# PSU_2.net
KiCad netlist of a schematic drawn in Altium Designer
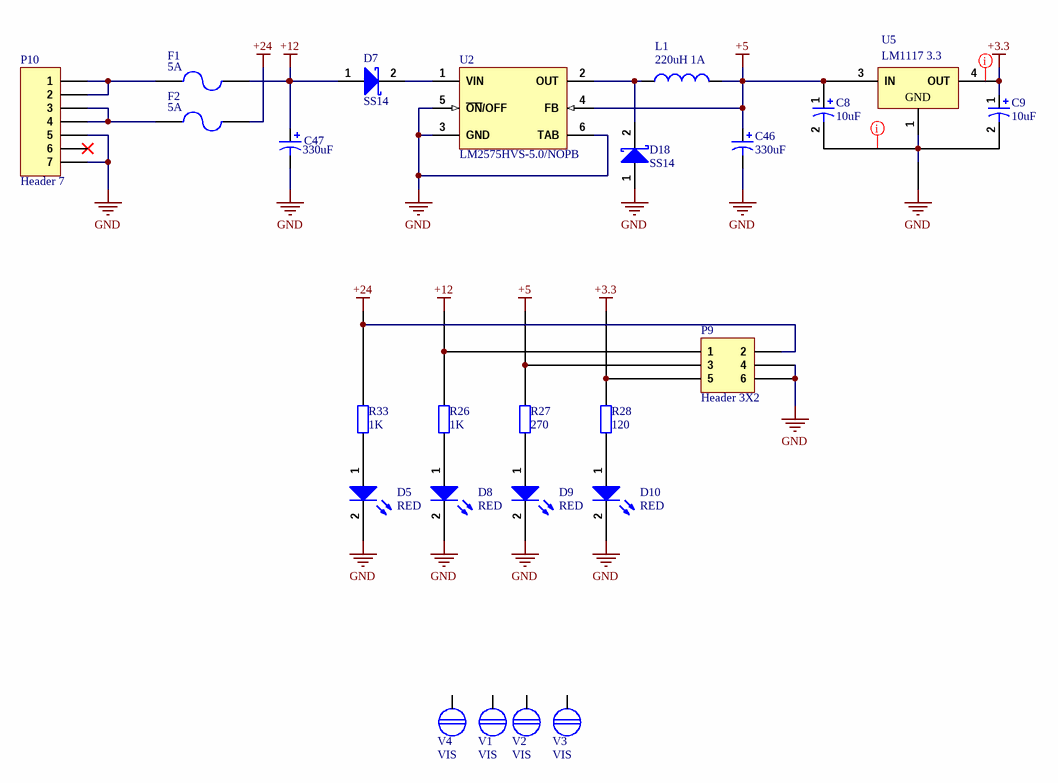
[diagram p0: PSU_2.SchDoc]

(export (version "E")
  (design (tool "Eeschema 10.0.6"))
  (components
    (comp (ref "C8")
      (value "10uF")
      (footprint "SYLANN:KEMET_4")
      (description "Polarized Capacitor")
      (fields
        (field (name "MANUFACTURER") "KEMET")
        (field (name "MANUFACTURER PART NUMBER") "EXV106M025A9BAA")
      )
      (libsource (lib "Miscellaneous Devices") (part "Cap Pol1"))
    )
    (comp (ref "C9")
      (value "10uF")
      (footprint "SYLANN:KEMET_4")
      (description "Polarized Capacitor")
      (fields
        (field (name "MANUFACTURER") "KEMET")
        (field (name "MANUFACTURER PART NUMBER") "EXV106M025A9BAA")
      )
      (libsource (lib "Miscellaneous Devices") (part "Cap Pol1"))
    )
    (comp (ref "C46")
      (value "330uF")
      (footprint "Kemet_10")
      (description "Polarized Capacitor (Radial)")
      (fields
        (field (name "MANUFACTURER") "KEMET")
        (field (name "MANUFACTURER PART NUMBER") "EDK337M025A9PAA")
      )
      (libsource (lib "") (part "Cap Pol1_1"))
    )
    (comp (ref "C47")
      (value "330uF")
      (footprint "Kemet_10")
      (description "Polarized Capacitor (Radial)")
      (fields
        (field (name "MANUFACTURER") "KEMET")
        (field (name "MANUFACTURER PART NUMBER") "EDK337M025A9PAA")
        (field (name "PUBLISHER") "Altium Limited")
      )
      (libsource (lib "") (part "Cap Pol1_1"))
    )
    (comp (ref "D5")
      (value "HSMH-C190")
      (footprint "SYLANN:0603-LEDR")
      (description "Surface Mount Chip LED, Red")
      (fields
        (field (name "MANUFACTURER") "AVAGO TECHNOLOGIES")
        (field (name "MANUFACTURER PART NUMBER") "HSMH-C190.")
        (field (name "COULEUR") "RED")
        (field (name "LONGUEUR/HAUTEUR") "1.6")
      )
      (libsource (lib "Avago Optoelectronic LED") (part "HSMH-C190"))
    )
    (comp (ref "D7")
      (value "SS14")
      (footprint "DO220AA")
      (description "Schottky Diode")
      (libsource (lib "MAIN BOARD CERES") (part "D Schottky"))
    )
    (comp (ref "D8")
      (value "HSMH-C190")
      (footprint "SYLANN:0603-LEDR")
      (description "Surface Mount Chip LED, Red")
      (fields
        (field (name "MANUFACTURER") "AVAGO TECHNOLOGIES")
        (field (name "MANUFACTURER PART NUMBER") "HSMH-C190.")
        (field (name "COULEUR") "RED")
        (field (name "LONGUEUR/HAUTEUR") "1.6")
      )
      (libsource (lib "Avago Optoelectronic LED") (part "HSMH-C190"))
    )
    (comp (ref "D9")
      (value "HSMH-C190")
      (footprint "SYLANN:0603-LEDR")
      (description "Surface Mount Chip LED, Red")
      (fields
        (field (name "MANUFACTURER") "AVAGO TECHNOLOGIES")
        (field (name "MANUFACTURER PART NUMBER") "HSMH-C190.")
        (field (name "COULEUR") "RED")
        (field (name "LONGUEUR/HAUTEUR") "1.6")
      )
      (libsource (lib "Avago Optoelectronic LED") (part "HSMH-C190"))
    )
    (comp (ref "D10")
      (value "HSMH-C190")
      (footprint "SYLANN:0603-LEDR")
      (description "Surface Mount Chip LED, Red")
      (fields
        (field (name "MANUFACTURER") "AVAGO TECHNOLOGIES")
        (field (name "MANUFACTURER PART NUMBER") "HSMH-C190.")
        (field (name "COULEUR") "RED")
        (field (name "LONGUEUR/HAUTEUR") "1.6")
      )
      (libsource (lib "Avago Optoelectronic LED") (part "HSMH-C190"))
    )
    (comp (ref "D18")
      (value "SS14")
      (footprint "DO220AA")
      (description "Schottky Diode")
      (libsource (lib "MAIN BOARD CERES") (part "D Schottky"))
    )
    (comp (ref "F1")
      (value "5A")
      (footprint "FUS5X20")
      (description "Fuse")
      (fields
        (field (name "MANUFACTURER") "KEYSTONE")
        (field (name "MANUFACTURER PART NUMBER") "4527")
        (field (name "PUBLISHER") "Altium Limited")
      )
      (libsource (lib "Miscellaneous Devices") (part "Fuse 2"))
    )
    (comp (ref "F2")
      (value "5A")
      (footprint "FUS5X20")
      (description "Fuse")
      (fields
        (field (name "MANUFACTURER") "KEYSTONE")
        (field (name "MANUFACTURER PART NUMBER") "4527")
        (field (name "PUBLISHER") "Altium Limited")
      )
      (libsource (lib "Miscellaneous Devices") (part "Fuse 2"))
    )
    (comp (ref "L1")
      (value "220uH 1A")
      (footprint "Self MCB 18X15")
      (description "Inductor")
      (fields
        (field (name "MANUFACTURER") "MULTICOMP")
        (field (name "MANUFACTURER PART NUMBER") "MCBFS7330-221MU")
        (field (name "LONGUEUR/HAUTEUR") "18.54")
      )
      (libsource (lib "Miscellaneous Devices") (part "Inductor"))
    )
    (comp (ref "P9")
      (value "Header 3X2")
      (footprint "M20-2X3")
      (description "Header, 3-Pin, Dual row")
      (fields
        (field (name "MANUFACTURER") "TE CONNECTIVITY / AMP")
        (field (name "MANUFACTURER PART NUMBER") "1241050-3")
        (field (name "PUBLISHER") "Altium Limited")
      )
      (libsource (lib "Miscellaneous Connectors") (part "Header 3X2"))
    )
    (comp (ref "P10")
      (value "Header 7")
      (footprint "CO7P508")
      (description "Header, 7-Pin")
      (fields (field (name "PUBLISHER") "Altium Limited"))
      (libsource (lib "Miscellaneous Connectors") (part "Header 7"))
    )
    (comp (ref "R26")
      (value "1K")
      (footprint "R0805")
      (description "Resistor")
      (fields
        (field (name "MANUFACTURER") "MULTICOMP")
        (field (name "MANUFACTURER PART NUMBER") "MC0.1W08051%1KFR")
      )
      (libsource (lib "BRA") (part "Resistor 0805 1K"))
    )
    (comp (ref "R27")
      (value "270")
      (footprint "R0805")
      (description "Resistor")
      (fields
        (field (name "MANUFACTURER") "MULTICOMP")
        (field (name "MANUFACTURER PART NUMBER") "MC01W08051270R")
      )
      (libsource (lib "BRA") (part "Resistor 0805 270"))
    )
    (comp (ref "R28")
      (value "120")
      (footprint "R0805")
      (description "Resistor")
      (fields
        (field (name "MANUFACTURER") "MULTICOMP")
        (field (name "MANUFACTURER PART NUMBER") "MC0.1W08051%1KFR")
      )
      (libsource (lib "BRA") (part "Resistor 0805 1K"))
    )
    (comp (ref "R33")
      (value "1K")
      (footprint "R0805")
      (description "Resistor")
      (fields
        (field (name "MANUFACTURER") "MULTICOMP")
        (field (name "MANUFACTURER PART NUMBER") "MC0.1W08051%1KFR")
      )
      (libsource (lib "BRA") (part "Resistor 0805 1K"))
    )
    (comp (ref "U2")
      (value "LM2575HVS-5.0/NOPB")
      (footprint "TO263-5")
      (description "SIMPLE SWITCHER® 1A Step-Down Voltage Regulator, 5-pin TO-263, Pb-Free")
      (fields
        (field (name "MANUFACTURER") "National Semiconductor")
        (field (name "PUBLISHER") "Altium Limited")
      )
      (libsource (lib "NSC Switcher") (part "LM2575HVS-5.0/NOPB"))
    )
    (comp (ref "U5")
      (value "LM1117 3.3")
      (footprint "TO252")
      (description "800mA Low-Dropout Linear Regulator, 3-pin TO-252")
      (fields
        (field (name "MANUFACTURER") "DIODES INC.")
        (field (name "MANUFACTURER PART NUMBER") "AP1117D33G-13")
      )
      (libsource (lib "Interface Lavazza blue") (part "LM1117DT-3.3"))
    )
    (comp (ref "V1") (value "VIS") (footprint "VIS42") (libsource (lib "UTIL_Library") (part "VIS")))
    (comp (ref "V2") (value "VIS") (footprint "VIS42") (libsource (lib "UTIL_Library") (part "VIS")))
    (comp (ref "V3") (value "VIS") (footprint "VIS42") (libsource (lib "UTIL_Library") (part "VIS")))
    (comp (ref "V4") (value "VIS") (footprint "VIS42") (libsource (lib "UTIL_Library") (part "VIS")))
  )
  (nets
    (net (code "1") (name "+3.3") (class "Default")
      (node (ref "C9") (pin "1") (pinfunction "1_1") (pintype "passive"))
      (node (ref "P9") (pin "5") (pinfunction "5_5") (pintype "passive"))
      (node (ref "R28") (pin "2") (pinfunction "2_2") (pintype "passive"))
      (node (ref "U5") (pin "4") (pinfunction "OUT_4") (pintype "power_in"))
    )
    (net (code "2") (name "+5") (class "Default")
      (node (ref "C46") (pin "1") (pinfunction "1_1") (pintype "passive"))
      (node (ref "C8") (pin "1") (pinfunction "1_1") (pintype "passive"))
      (node (ref "L1") (pin "2") (pinfunction "2_2") (pintype "passive"))
      (node (ref "P9") (pin "3") (pinfunction "3_3") (pintype "passive"))
      (node (ref "R27") (pin "2") (pinfunction "2_2") (pintype "passive"))
      (node (ref "U2") (pin "4") (pinfunction "FB_4") (pintype "input"))
      (node (ref "U5") (pin "3") (pinfunction "IN_3") (pintype "power_in"))
    )
    (net (code "3") (name "+12") (class "Default")
      (node (ref "C47") (pin "1") (pinfunction "1_1") (pintype "passive"))
      (node (ref "D7") (pin "1") (pinfunction "A_1") (pintype "passive"))
      (node (ref "F1") (pin "2") (pinfunction "2_2") (pintype "passive"))
      (node (ref "P9") (pin "1") (pinfunction "1_1") (pintype "passive"))
      (node (ref "R26") (pin "2") (pinfunction "2_2") (pintype "passive"))
    )
    (net (code "4") (name "+24") (class "Default")
      (node (ref "F2") (pin "2") (pinfunction "2_2") (pintype "passive"))
      (node (ref "P9") (pin "2") (pinfunction "2_2") (pintype "passive"))
      (node (ref "R33") (pin "2") (pinfunction "2_2") (pintype "passive"))
    )
    (net (code "5") (name "GND") (class "Default")
      (node (ref "C46") (pin "2") (pinfunction "2_2") (pintype "passive"))
      (node (ref "C47") (pin "2") (pinfunction "2_2") (pintype "passive"))
      (node (ref "C8") (pin "2") (pinfunction "2_2") (pintype "passive"))
      (node (ref "C9") (pin "2") (pinfunction "2_2") (pintype "passive"))
      (node (ref "D10") (pin "2") (pinfunction "K_2") (pintype "passive"))
      (node (ref "D18") (pin "1") (pinfunction "A_1") (pintype "passive"))
      (node (ref "D5") (pin "2") (pinfunction "K_2") (pintype "passive"))
      (node (ref "D8") (pin "2") (pinfunction "K_2") (pintype "passive"))
      (node (ref "D9") (pin "2") (pinfunction "K_2") (pintype "passive"))
      (node (ref "P10") (pin "5") (pinfunction "5_5") (pintype "passive"))
      (node (ref "P10") (pin "7") (pinfunction "7_7") (pintype "passive"))
      (node (ref "P9") (pin "4") (pinfunction "4_4") (pintype "passive"))
      (node (ref "P9") (pin "6") (pinfunction "6_6") (pintype "passive"))
      (node (ref "U2") (pin "3") (pinfunction "GND_3") (pintype "power_in"))
      (node (ref "U2") (pin "5") (pinfunction "~{ON}/OFF_5") (pintype "input"))
      (node (ref "U2") (pin "6") (pinfunction "TAB_6") (pintype "power_in"))
      (node (ref "U5") (pin "1") (pinfunction "GND_1") (pintype "power_in"))
    )
    (net (code "6") (name "Net-(D5-A)") (class "Default")
      (node (ref "D5") (pin "1") (pinfunction "A_1") (pintype "passive"))
      (node (ref "R33") (pin "1") (pinfunction "1_1") (pintype "passive"))
    )
    (net (code "7") (name "Net-(D7-K)") (class "Default")
      (node (ref "D7") (pin "2") (pinfunction "K_2") (pintype "passive"))
      (node (ref "U2") (pin "1") (pinfunction "VIN_1") (pintype "power_in"))
    )
    (net (code "8") (name "Net-(D8-A)") (class "Default")
      (node (ref "D8") (pin "1") (pinfunction "A_1") (pintype "passive"))
      (node (ref "R26") (pin "1") (pinfunction "1_1") (pintype "passive"))
    )
    (net (code "9") (name "Net-(D9-A)") (class "Default")
      (node (ref "D9") (pin "1") (pinfunction "A_1") (pintype "passive"))
      (node (ref "R27") (pin "1") (pinfunction "1_1") (pintype "passive"))
    )
    (net (code "10") (name "Net-(D10-A)") (class "Default")
      (node (ref "D10") (pin "1") (pinfunction "A_1") (pintype "passive"))
      (node (ref "R28") (pin "1") (pinfunction "1_1") (pintype "passive"))
    )
    (net (code "11") (name "Net-(D18-K)") (class "Default")
      (node (ref "D18") (pin "2") (pinfunction "K_2") (pintype "passive"))
      (node (ref "L1") (pin "1") (pinfunction "1_1") (pintype "passive"))
      (node (ref "U2") (pin "2") (pinfunction "OUT_2") (pintype "power_in"))
    )
    (net (code "12") (name "Net-(F1-Pad1)") (class "Default")
      (node (ref "F1") (pin "1") (pinfunction "1_1") (pintype "passive"))
      (node (ref "P10") (pin "1") (pinfunction "1_1") (pintype "passive"))
      (node (ref "P10") (pin "2") (pinfunction "2_2") (pintype "passive"))
    )
    (net (code "13") (name "Net-(F2-Pad1)") (class "Default")
      (node (ref "F2") (pin "1") (pinfunction "1_1") (pintype "passive"))
      (node (ref "P10") (pin "3") (pinfunction "3_3") (pintype "passive"))
      (node (ref "P10") (pin "4") (pinfunction "4_4") (pintype "passive"))
    )
    (net (code "14") (name "unconnected-(P10-Pad6)") (class "Default")
      (node (ref "P10") (pin "6") (pinfunction "6_6") (pintype "passive+no_connect"))
    )
    (net (code "15") (name "unconnected-(V1-Pad1)") (class "Default")
      (node (ref "V1") (pin "1") (pinfunction "1_1") (pintype "passive"))
    )
    (net (code "16") (name "unconnected-(V2-Pad1)") (class "Default")
      (node (ref "V2") (pin "1") (pinfunction "1_1") (pintype "passive"))
    )
    (net (code "17") (name "unconnected-(V3-Pad1)") (class "Default")
      (node (ref "V3") (pin "1") (pinfunction "1_1") (pintype "passive"))
    )
    (net (code "18") (name "unconnected-(V4-Pad1)") (class "Default")
      (node (ref "V4") (pin "1") (pinfunction "1_1") (pintype "passive"))
    )
  )
)
